# Connector_Section.net
KiCad netlist of a schematic drawn in Altium Designer
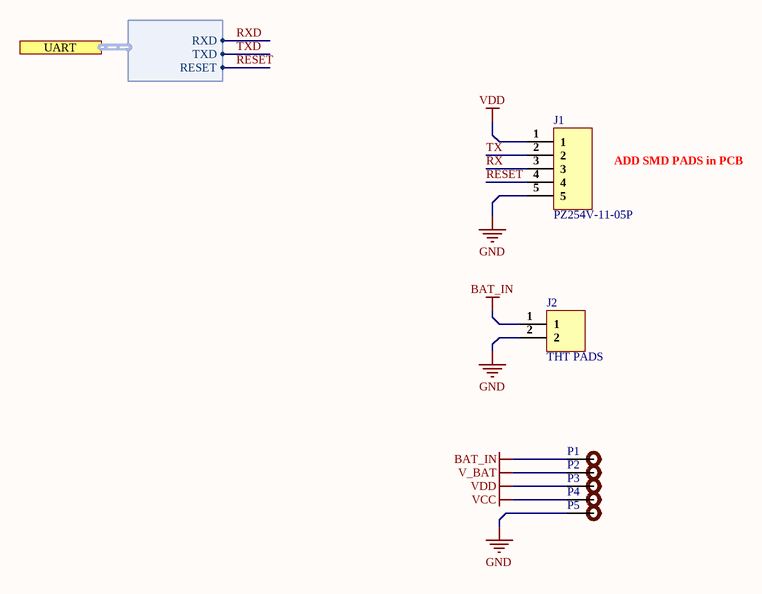
[diagram p0: Connector Section.SchDoc]

(export (version "E")
  (design (tool "Eeschema 10.0.6"))
  (components
    (comp (ref "J1")
      (value "PZ254V-11-05P")
      (footprint "PZ254V-11-05P")
      (description "Pin Header 5 1 right-angle")
      (fields (field (name "MANUFACTURER") "XFCN"))
      (libsource (lib "TT_IntLib") (part "PZ254V-11-05P"))
    )
    (comp (ref "J2") (value "THT PADS") (footprint "THT PAD") (libsource (lib "TT_IntLib") (part "THT PAD")))
    (comp (ref "P1")
      (value "Test Point")
      (footprint "TEST POINT")
      (description "Test Point ON")
      (libsource (lib "TT_IntLib") (part "TEST POINT"))
    )
    (comp (ref "P2")
      (value "Test Point")
      (footprint "TEST POINT")
      (description "Test Point ON")
      (libsource (lib "TT_IntLib") (part "TEST POINT"))
    )
    (comp (ref "P3")
      (value "Test Point")
      (footprint "TEST POINT")
      (description "Test Point ON")
      (libsource (lib "TT_IntLib") (part "TEST POINT"))
    )
    (comp (ref "P4")
      (value "Test Point")
      (footprint "TEST POINT")
      (description "Test Point ON")
      (libsource (lib "TT_IntLib") (part "TEST POINT"))
    )
    (comp (ref "P5")
      (value "Test Point")
      (footprint "TEST POINT")
      (description "Test Point ON")
      (libsource (lib "TT_IntLib") (part "TEST POINT"))
    )
  )
  (nets
    (net (code "2") (name "/RESET") (class "Default")
      (node (ref "J1") (pin "4") (pinfunction "4_4") (pintype "passive"))
    )
    (net (code "3") (name "/RX") (class "Default")
      (node (ref "J1") (pin "3") (pinfunction "3_3") (pintype "passive"))
    )
    (net (code "5") (name "/TX") (class "Default")
      (node (ref "J1") (pin "2") (pinfunction "2_2") (pintype "passive"))
    )
    (net (code "8") (name "BAT_IN") (class "Default")
      (node (ref "J2") (pin "1") (pinfunction "1_1") (pintype "passive"))
      (node (ref "P1") (pin "1") (pinfunction "1_1") (pintype "passive"))
    )
    (net (code "9") (name "GND") (class "Default")
      (node (ref "J1") (pin "5") (pinfunction "5_5") (pintype "passive"))
      (node (ref "J2") (pin "2") (pinfunction "2_2") (pintype "passive"))
      (node (ref "P5") (pin "1") (pinfunction "1_1") (pintype "passive"))
    )
    (net (code "10") (name "VCC") (class "Default")
      (node (ref "P4") (pin "1") (pinfunction "1_1") (pintype "passive"))
    )
    (net (code "11") (name "VDD") (class "Default")
      (node (ref "J1") (pin "1") (pinfunction "1_1") (pintype "passive"))
      (node (ref "P3") (pin "1") (pinfunction "1_1") (pintype "passive"))
    )
    (net (code "12") (name "V_BAT") (class "Default")
      (node (ref "P2") (pin "1") (pinfunction "1_1") (pintype "passive"))
    )
  )
)
